# inv_schem.net
KiCad netlist of a schematic drawn in Altium Designer
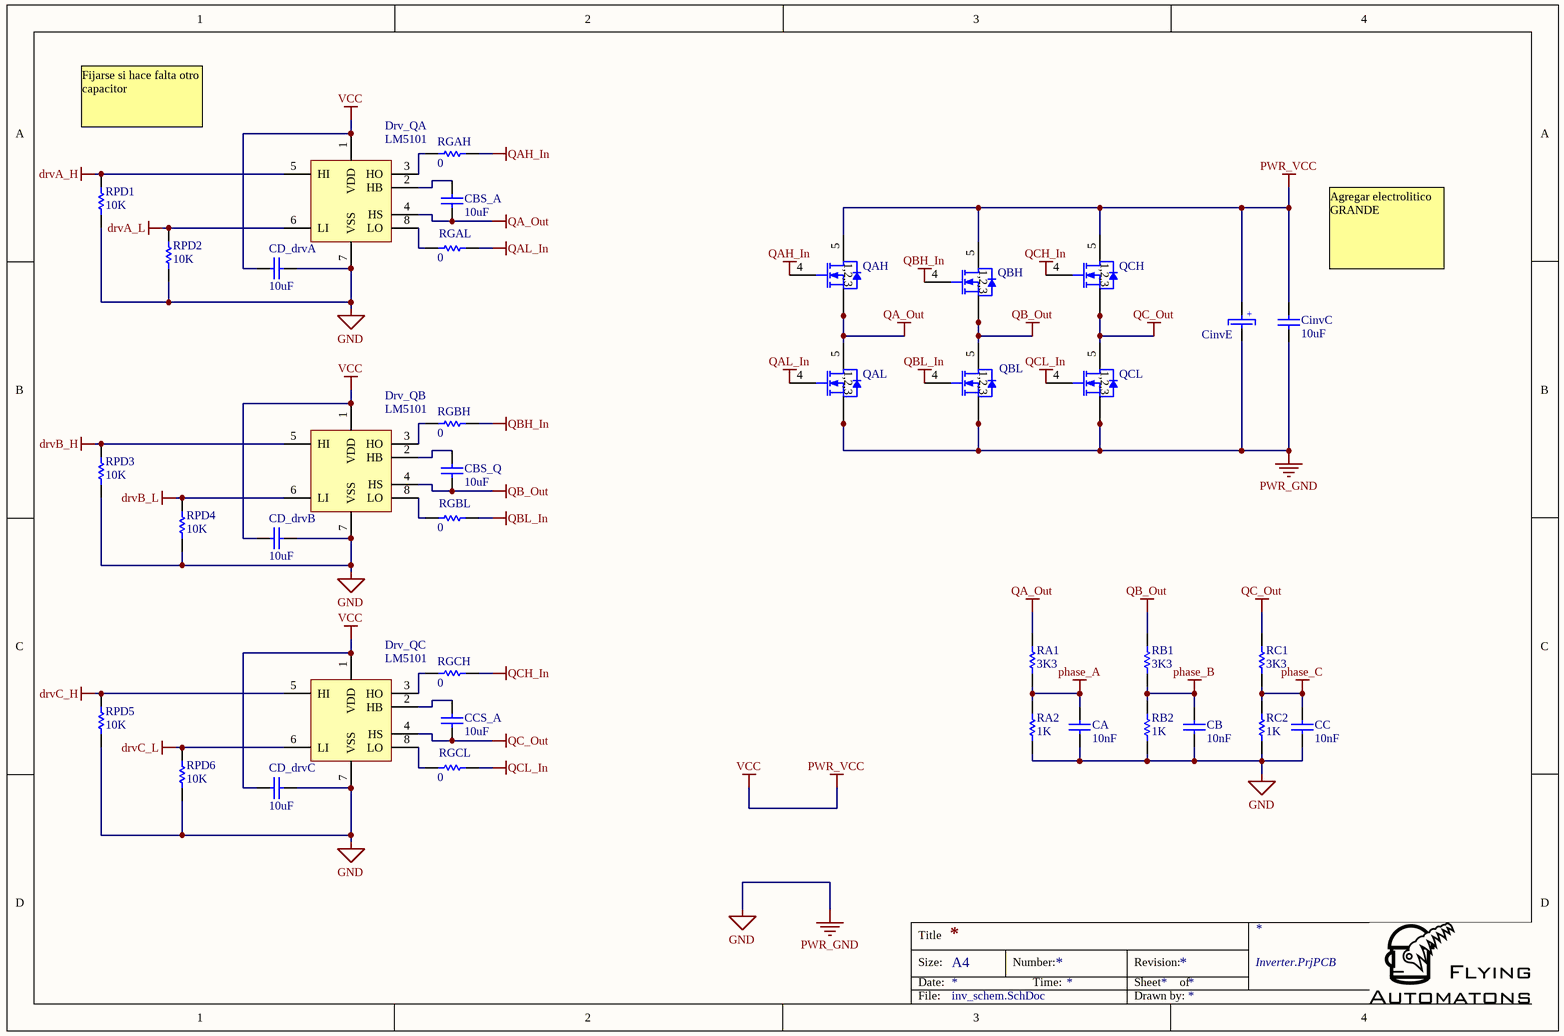
[diagram p0: inv_schem.SchDoc]

(export (version "E")
  (design (tool "Eeschema 10.0.6"))
  (components
    (comp (ref "CA")
      (value "10nF")
      (footprint "CAPC1608L")
      (description "CAP CER 0.1UF 50V Y5V 0603")
      (fields (field (name "MANUFACTURER PART NUMBER") "CC0603ZRY5V9BB104"))
      (libsource (lib "Passive#csv") (part "CAP_100n_0603_50V_Y5V"))
    )
    (comp (ref "CB")
      (value "10nF")
      (footprint "CAPC1608L")
      (description "CAP CER 0.1UF 50V Y5V 0603")
      (fields (field (name "MANUFACTURER PART NUMBER") "CC0603ZRY5V9BB104"))
      (libsource (lib "Passive#csv") (part "CAP_100n_0603_50V_Y5V"))
    )
    (comp (ref "CBS_A")
      (value "10uF")
      (footprint "CAPC3216L")
      (description "CAP CER 10UF 25V Y5V 1206")
      (fields (field (name "MANUFACTURER PART NUMBER") "TMK316F106ZL-T"))
      (libsource (lib "Passive#csv") (part "CAP_10u_1206_25V_Y5V"))
    )
    (comp (ref "CBS_Q")
      (value "10uF")
      (footprint "CAPC3216L")
      (description "CAP CER 10UF 25V Y5V 1206")
      (fields (field (name "MANUFACTURER PART NUMBER") "TMK316F106ZL-T"))
      (libsource (lib "Passive#csv") (part "CAP_10u_1206_25V_Y5V"))
    )
    (comp (ref "CC")
      (value "10nF")
      (footprint "CAPC1608L")
      (description "CAP CER 0.1UF 50V Y5V 0603")
      (fields (field (name "MANUFACTURER PART NUMBER") "CC0603ZRY5V9BB104"))
      (libsource (lib "Passive#csv") (part "CAP_100n_0603_50V_Y5V"))
    )
    (comp (ref "CCS_A")
      (value "10uF")
      (footprint "CAPC3216L")
      (description "CAP CER 10UF 25V Y5V 1206")
      (fields (field (name "MANUFACTURER PART NUMBER") "TMK316F106ZL-T"))
      (libsource (lib "Passive#csv") (part "CAP_10u_1206_25V_Y5V"))
    )
    (comp (ref "CD_drvA")
      (value "10uF")
      (footprint "CAPC3216L")
      (description "CAP CER 10UF 25V Y5V 1206")
      (fields (field (name "MANUFACTURER PART NUMBER") "TMK316F106ZL-T"))
      (libsource (lib "Passive#csv") (part "CAP_10u_1206_25V_Y5V"))
    )
    (comp (ref "CD_drvB")
      (value "10uF")
      (footprint "CAPC3216L")
      (description "CAP CER 10UF 25V Y5V 1206")
      (fields (field (name "MANUFACTURER PART NUMBER") "TMK316F106ZL-T"))
      (libsource (lib "Passive#csv") (part "CAP_10u_1206_25V_Y5V"))
    )
    (comp (ref "CD_drvC")
      (value "10uF")
      (footprint "CAPC3216L")
      (description "CAP CER 10UF 25V Y5V 1206")
      (fields (field (name "MANUFACTURER PART NUMBER") "TMK316F106ZL-T"))
      (libsource (lib "Passive#csv") (part "CAP_10u_1206_25V_Y5V"))
    )
    (comp (ref "CinvC")
      (value "10uF")
      (footprint "CAPC3216L")
      (description "CAP CER 10UF 25V Y5V 1206")
      (fields (field (name "MANUFACTURER PART NUMBER") "TMK316F106ZL-T"))
      (libsource (lib "Passive#csv") (part "CAP_10u_1206_25V_Y5V"))
    )
    (comp (ref "CinvE")
      (value "SMD_ECap")
      (footprint "SMD ECap")
      (description "100uF")
      (libsource (lib "smd") (part "SMD_ECap"))
    )
    (comp (ref "Drv_QA")
      (value "LM5101")
      (footprint "JEDEC_MS-012AA")
      (description "100V 2A N-Channel MOSFET Gate Driver")
      (fields
        (field (name "MANUFACTURER PART NUMBER") "LM5101BMA-NOPB")
        (field (name "MANUFACTURER") "Texas Instruments")
      )
      (libsource (lib "Power_IC#csv") (part "LM5101"))
    )
    (comp (ref "Drv_QB")
      (value "LM5101")
      (footprint "JEDEC_MS-012AA")
      (description "100V 2A N-Channel MOSFET Gate Driver")
      (fields
        (field (name "MANUFACTURER PART NUMBER") "LM5101BMA-NOPB")
        (field (name "MANUFACTURER") "Texas Instruments")
      )
      (libsource (lib "Power_IC#csv") (part "LM5101"))
    )
    (comp (ref "Drv_QC")
      (value "LM5101")
      (footprint "JEDEC_MS-012AA")
      (description "100V 2A N-Channel MOSFET Gate Driver")
      (fields
        (field (name "MANUFACTURER PART NUMBER") "LM5101BMA-NOPB")
        (field (name "MANUFACTURER") "Texas Instruments")
      )
      (libsource (lib "Power_IC#csv") (part "LM5101"))
    )
    (comp (ref "QAH")
      (value "~")
      (footprint "x-NXP_LFPAK33")
      (description "TRANSISTOR MOSFET N-CHANN 25V 8.6MOHM")
      (fields
        (field (name "MANUFACTURER") "NXP Semiconductors")
        (field (name "MANUFACTURER PART NUMBER") "PSMN9R0-25MLC,115")
      )
      (libsource (lib "Discrete#csv") (part "PSMN9R0-25MLC"))
    )
    (comp (ref "QAL")
      (value "~")
      (footprint "x-NXP_LFPAK33")
      (description "TRANSISTOR MOSFET N-CHANN 25V 8.6MOHM")
      (fields
        (field (name "MANUFACTURER") "NXP Semiconductors")
        (field (name "MANUFACTURER PART NUMBER") "PSMN9R0-25MLC,115")
      )
      (libsource (lib "Discrete#csv") (part "PSMN9R0-25MLC"))
    )
    (comp (ref "QBH")
      (value "~")
      (footprint "x-NXP_LFPAK33")
      (description "TRANSISTOR MOSFET N-CHANN 25V 8.6MOHM")
      (fields
        (field (name "MANUFACTURER") "NXP Semiconductors")
        (field (name "MANUFACTURER PART NUMBER") "PSMN9R0-25MLC,115")
      )
      (libsource (lib "Discrete#csv") (part "PSMN9R0-25MLC"))
    )
    (comp (ref "QBL")
      (value "~")
      (footprint "x-NXP_LFPAK33")
      (description "TRANSISTOR MOSFET N-CHANN 25V 8.6MOHM")
      (fields
        (field (name "MANUFACTURER") "NXP Semiconductors")
        (field (name "MANUFACTURER PART NUMBER") "PSMN9R0-25MLC,115")
      )
      (libsource (lib "Discrete#csv") (part "PSMN9R0-25MLC"))
    )
    (comp (ref "QCH")
      (value "~")
      (footprint "x-NXP_LFPAK33")
      (description "TRANSISTOR MOSFET N-CHANN 25V 8.6MOHM")
      (fields
        (field (name "MANUFACTURER") "NXP Semiconductors")
        (field (name "MANUFACTURER PART NUMBER") "PSMN9R0-25MLC,115")
      )
      (libsource (lib "Discrete#csv") (part "PSMN9R0-25MLC"))
    )
    (comp (ref "QCL")
      (value "~")
      (footprint "x-NXP_LFPAK33")
      (description "TRANSISTOR MOSFET N-CHANN 25V 8.6MOHM")
      (fields
        (field (name "MANUFACTURER") "NXP Semiconductors")
        (field (name "MANUFACTURER PART NUMBER") "PSMN9R0-25MLC,115")
      )
      (libsource (lib "Discrete#csv") (part "PSMN9R0-25MLC"))
    )
    (comp (ref "RA1")
      (value "3K3")
      (footprint "RESC1608L")
      (description "RES 1K OHM 1/10W 5% 0603")
      (fields (field (name "MANUFACTURER PART NUMBER") "RMCF0603JT1K00"))
      (libsource (lib "Passive#csv") (part "RES_1K_0603_0W1_1%"))
    )
    (comp (ref "RA2")
      (value "1K")
      (footprint "RESC1608L")
      (description "RES 1K OHM 1/10W 5% 0603")
      (fields (field (name "MANUFACTURER PART NUMBER") "RMCF0603JT1K00"))
      (libsource (lib "Passive#csv") (part "RES_1K_0603_0W1_1%"))
    )
    (comp (ref "RB1")
      (value "3K3")
      (footprint "RESC1608L")
      (description "RES 1K OHM 1/10W 5% 0603")
      (fields (field (name "MANUFACTURER PART NUMBER") "RMCF0603JT1K00"))
      (libsource (lib "Passive#csv") (part "RES_1K_0603_0W1_1%"))
    )
    (comp (ref "RB2")
      (value "1K")
      (footprint "RESC1608L")
      (description "RES 1K OHM 1/10W 5% 0603")
      (fields (field (name "MANUFACTURER PART NUMBER") "RMCF0603JT1K00"))
      (libsource (lib "Passive#csv") (part "RES_1K_0603_0W1_1%"))
    )
    (comp (ref "RC1")
      (value "3K3")
      (footprint "RESC1608L")
      (description "RES 1K OHM 1/10W 5% 0603")
      (fields (field (name "MANUFACTURER PART NUMBER") "RMCF0603JT1K00"))
      (libsource (lib "Passive#csv") (part "RES_1K_0603_0W1_1%"))
    )
    (comp (ref "RC2")
      (value "1K")
      (footprint "RESC1608L")
      (description "RES 1K OHM 1/10W 5% 0603")
      (fields (field (name "MANUFACTURER PART NUMBER") "RMCF0603JT1K00"))
      (libsource (lib "Passive#csv") (part "RES_1K_0603_0W1_1%"))
    )
    (comp (ref "RGAH")
      (value "0")
      (footprint "RESC1608L")
      (description "RES 0.0 OHM 1/10W JUMP 0603")
      (fields (field (name "MANUFACTURER PART NUMBER") "RC1608J000CS"))
      (libsource (lib "Passive#csv") (part "RES_0_0603_0W1_1%"))
    )
    (comp (ref "RGAL")
      (value "0")
      (footprint "RESC1608L")
      (description "RES 0.0 OHM 1/10W JUMP 0603")
      (fields (field (name "MANUFACTURER PART NUMBER") "RC1608J000CS"))
      (libsource (lib "Passive#csv") (part "RES_0_0603_0W1_1%"))
    )
    (comp (ref "RGBH")
      (value "0")
      (footprint "RESC1608L")
      (description "RES 0.0 OHM 1/10W JUMP 0603")
      (fields (field (name "MANUFACTURER PART NUMBER") "RC1608J000CS"))
      (libsource (lib "Passive#csv") (part "RES_0_0603_0W1_1%"))
    )
    (comp (ref "RGBL")
      (value "0")
      (footprint "RESC1608L")
      (description "RES 0.0 OHM 1/10W JUMP 0603")
      (fields (field (name "MANUFACTURER PART NUMBER") "RC1608J000CS"))
      (libsource (lib "Passive#csv") (part "RES_0_0603_0W1_1%"))
    )
    (comp (ref "RGCH")
      (value "0")
      (footprint "RESC1608L")
      (description "RES 0.0 OHM 1/10W JUMP 0603")
      (fields (field (name "MANUFACTURER PART NUMBER") "RC1608J000CS"))
      (libsource (lib "Passive#csv") (part "RES_0_0603_0W1_1%"))
    )
    (comp (ref "RGCL")
      (value "0")
      (footprint "RESC1608L")
      (description "RES 0.0 OHM 1/10W JUMP 0603")
      (fields (field (name "MANUFACTURER PART NUMBER") "RC1608J000CS"))
      (libsource (lib "Passive#csv") (part "RES_0_0603_0W1_1%"))
    )
    (comp (ref "RPD1")
      (value "10K")
      (footprint "RESC1608L")
      (description "RES 10K OHM 1/10W 5% 0603")
      (fields (field (name "MANUFACTURER PART NUMBER") "RC1608J103CS"))
      (libsource (lib "Passive#csv") (part "RES_10K_0603_0W1_1%"))
    )
    (comp (ref "RPD2")
      (value "10K")
      (footprint "RESC1608L")
      (description "RES 10K OHM 1/10W 5% 0603")
      (fields (field (name "MANUFACTURER PART NUMBER") "RC1608J103CS"))
      (libsource (lib "Passive#csv") (part "RES_10K_0603_0W1_1%"))
    )
    (comp (ref "RPD3")
      (value "10K")
      (footprint "RESC1608L")
      (description "RES 10K OHM 1/10W 5% 0603")
      (fields (field (name "MANUFACTURER PART NUMBER") "RC1608J103CS"))
      (libsource (lib "Passive#csv") (part "RES_10K_0603_0W1_1%"))
    )
    (comp (ref "RPD4")
      (value "10K")
      (footprint "RESC1608L")
      (description "RES 10K OHM 1/10W 5% 0603")
      (fields (field (name "MANUFACTURER PART NUMBER") "RC1608J103CS"))
      (libsource (lib "Passive#csv") (part "RES_10K_0603_0W1_1%"))
    )
    (comp (ref "RPD5")
      (value "10K")
      (footprint "RESC1608L")
      (description "RES 10K OHM 1/10W 5% 0603")
      (fields (field (name "MANUFACTURER PART NUMBER") "RC1608J103CS"))
      (libsource (lib "Passive#csv") (part "RES_10K_0603_0W1_1%"))
    )
    (comp (ref "RPD6")
      (value "10K")
      (footprint "RESC1608L")
      (description "RES 10K OHM 1/10W 5% 0603")
      (fields (field (name "MANUFACTURER PART NUMBER") "RC1608J103CS"))
      (libsource (lib "Passive#csv") (part "RES_10K_0603_0W1_1%"))
    )
  )
  (nets
    (net (code "1") (name "GND") (class "Default")
      (node (ref "CA") (pin "2") (pinfunction "2_2") (pintype "passive"))
      (node (ref "CB") (pin "2") (pinfunction "2_2") (pintype "passive"))
      (node (ref "CC") (pin "2") (pinfunction "2_2") (pintype "passive"))
      (node (ref "CD_drvA") (pin "2") (pinfunction "2_2") (pintype "passive"))
      (node (ref "CD_drvB") (pin "2") (pinfunction "2_2") (pintype "passive"))
      (node (ref "CD_drvC") (pin "2") (pinfunction "2_2") (pintype "passive"))
      (node (ref "CinvC") (pin "2") (pinfunction "2_2") (pintype "passive"))
      (node (ref "CinvE") (pin "2") (pinfunction "2_2") (pintype "passive"))
      (node (ref "Drv_QA") (pin "7") (pinfunction "VSS_7") (pintype "passive"))
      (node (ref "Drv_QB") (pin "7") (pinfunction "VSS_7") (pintype "passive"))
      (node (ref "Drv_QC") (pin "7") (pinfunction "VSS_7") (pintype "passive"))
      (node (ref "QAL") (pin "1") (pinfunction "S_1") (pintype "passive"))
      (node (ref "QAL") (pin "2") (pinfunction "S_2") (pintype "passive"))
      (node (ref "QAL") (pin "3") (pinfunction "S_3") (pintype "passive"))
      (node (ref "QBL") (pin "1") (pinfunction "S_1") (pintype "passive"))
      (node (ref "QBL") (pin "2") (pinfunction "S_2") (pintype "passive"))
      (node (ref "QBL") (pin "3") (pinfunction "S_3") (pintype "passive"))
      (node (ref "QCL") (pin "1") (pinfunction "S_1") (pintype "passive"))
      (node (ref "QCL") (pin "2") (pinfunction "S_2") (pintype "passive"))
      (node (ref "QCL") (pin "3") (pinfunction "S_3") (pintype "passive"))
      (node (ref "RA2") (pin "2") (pinfunction "2_2") (pintype "passive"))
      (node (ref "RB2") (pin "2") (pinfunction "2_2") (pintype "passive"))
      (node (ref "RC2") (pin "2") (pinfunction "2_2") (pintype "passive"))
      (node (ref "RPD1") (pin "2") (pinfunction "2_2") (pintype "passive"))
      (node (ref "RPD2") (pin "2") (pinfunction "2_2") (pintype "passive"))
      (node (ref "RPD3") (pin "2") (pinfunction "2_2") (pintype "passive"))
      (node (ref "RPD4") (pin "2") (pinfunction "2_2") (pintype "passive"))
      (node (ref "RPD5") (pin "2") (pinfunction "2_2") (pintype "passive"))
      (node (ref "RPD6") (pin "2") (pinfunction "2_2") (pintype "passive"))
    )
    (net (code "2") (name "Net-(Drv_QA-HB)") (class "Default")
      (node (ref "CBS_A") (pin "1") (pinfunction "1_1") (pintype "passive"))
      (node (ref "Drv_QA") (pin "2") (pinfunction "HB_2") (pintype "passive"))
    )
    (net (code "3") (name "Net-(Drv_QA-HO)") (class "Default")
      (node (ref "Drv_QA") (pin "3") (pinfunction "HO_3") (pintype "passive"))
      (node (ref "RGAH") (pin "2") (pinfunction "2_2") (pintype "passive"))
    )
    (net (code "4") (name "Net-(Drv_QA-LO)") (class "Default")
      (node (ref "Drv_QA") (pin "8") (pinfunction "LO_8") (pintype "passive"))
      (node (ref "RGAL") (pin "2") (pinfunction "2_2") (pintype "passive"))
    )
    (net (code "5") (name "Net-(Drv_QB-HB)") (class "Default")
      (node (ref "CBS_Q") (pin "1") (pinfunction "1_1") (pintype "passive"))
      (node (ref "Drv_QB") (pin "2") (pinfunction "HB_2") (pintype "passive"))
    )
    (net (code "6") (name "Net-(Drv_QB-HO)") (class "Default")
      (node (ref "Drv_QB") (pin "3") (pinfunction "HO_3") (pintype "passive"))
      (node (ref "RGBH") (pin "2") (pinfunction "2_2") (pintype "passive"))
    )
    (net (code "7") (name "Net-(Drv_QB-LO)") (class "Default")
      (node (ref "Drv_QB") (pin "8") (pinfunction "LO_8") (pintype "passive"))
      (node (ref "RGBL") (pin "2") (pinfunction "2_2") (pintype "passive"))
    )
    (net (code "8") (name "Net-(Drv_QC-HB)") (class "Default")
      (node (ref "CCS_A") (pin "1") (pinfunction "1_1") (pintype "passive"))
      (node (ref "Drv_QC") (pin "2") (pinfunction "HB_2") (pintype "passive"))
    )
    (net (code "9") (name "Net-(Drv_QC-HO)") (class "Default")
      (node (ref "Drv_QC") (pin "3") (pinfunction "HO_3") (pintype "passive"))
      (node (ref "RGCH") (pin "2") (pinfunction "2_2") (pintype "passive"))
    )
    (net (code "10") (name "Net-(Drv_QC-LO)") (class "Default")
      (node (ref "Drv_QC") (pin "8") (pinfunction "LO_8") (pintype "passive"))
      (node (ref "RGCL") (pin "2") (pinfunction "2_2") (pintype "passive"))
    )
    (net (code "11") (name "PWR_VCC") (class "Default")
      (node (ref "CD_drvA") (pin "1") (pinfunction "1_1") (pintype "passive"))
      (node (ref "CD_drvB") (pin "1") (pinfunction "1_1") (pintype "passive"))
      (node (ref "CD_drvC") (pin "1") (pinfunction "1_1") (pintype "passive"))
      (node (ref "CinvC") (pin "1") (pinfunction "1_1") (pintype "passive"))
      (node (ref "CinvE") (pin "1") (pinfunction "1_1") (pintype "passive"))
      (node (ref "Drv_QA") (pin "1") (pinfunction "VDD_1") (pintype "passive"))
      (node (ref "Drv_QB") (pin "1") (pinfunction "VDD_1") (pintype "passive"))
      (node (ref "Drv_QC") (pin "1") (pinfunction "VDD_1") (pintype "passive"))
      (node (ref "QAH") (pin "5") (pinfunction "D_5") (pintype "passive"))
      (node (ref "QBH") (pin "5") (pinfunction "D_5") (pintype "passive"))
      (node (ref "QCH") (pin "5") (pinfunction "D_5") (pintype "passive"))
    )
    (net (code "12") (name "QAH_In") (class "Default")
      (node (ref "QAH") (pin "4") (pinfunction "G_4") (pintype "passive"))
      (node (ref "RGAH") (pin "1") (pinfunction "1_1") (pintype "passive"))
    )
    (net (code "13") (name "QAL_In") (class "Default")
      (node (ref "QAL") (pin "4") (pinfunction "G_4") (pintype "passive"))
      (node (ref "RGAL") (pin "1") (pinfunction "1_1") (pintype "passive"))
    )
    (net (code "14") (name "QA_Out") (class "Default")
      (node (ref "CBS_A") (pin "2") (pinfunction "2_2") (pintype "passive"))
      (node (ref "Drv_QA") (pin "4") (pinfunction "HS_4") (pintype "passive"))
      (node (ref "QAH") (pin "1") (pinfunction "S_1") (pintype "passive"))
      (node (ref "QAH") (pin "2") (pinfunction "S_2") (pintype "passive"))
      (node (ref "QAH") (pin "3") (pinfunction "S_3") (pintype "passive"))
      (node (ref "QAL") (pin "5") (pinfunction "D_5") (pintype "passive"))
      (node (ref "RA1") (pin "1") (pinfunction "1_1") (pintype "passive"))
    )
    (net (code "15") (name "QBH_In") (class "Default")
      (node (ref "QBH") (pin "4") (pinfunction "G_4") (pintype "passive"))
      (node (ref "RGBH") (pin "1") (pinfunction "1_1") (pintype "passive"))
    )
    (net (code "16") (name "QBL_In") (class "Default")
      (node (ref "QBL") (pin "4") (pinfunction "G_4") (pintype "passive"))
      (node (ref "RGBL") (pin "1") (pinfunction "1_1") (pintype "passive"))
    )
    (net (code "17") (name "QB_Out") (class "Default")
      (node (ref "CBS_Q") (pin "2") (pinfunction "2_2") (pintype "passive"))
      (node (ref "Drv_QB") (pin "4") (pinfunction "HS_4") (pintype "passive"))
      (node (ref "QBH") (pin "1") (pinfunction "S_1") (pintype "passive"))
      (node (ref "QBH") (pin "2") (pinfunction "S_2") (pintype "passive"))
      (node (ref "QBH") (pin "3") (pinfunction "S_3") (pintype "passive"))
      (node (ref "QBL") (pin "5") (pinfunction "D_5") (pintype "passive"))
      (node (ref "RB1") (pin "1") (pinfunction "1_1") (pintype "passive"))
    )
    (net (code "18") (name "QCH_In") (class "Default")
      (node (ref "QCH") (pin "4") (pinfunction "G_4") (pintype "passive"))
      (node (ref "RGCH") (pin "1") (pinfunction "1_1") (pintype "passive"))
    )
    (net (code "19") (name "QCL_In") (class "Default")
      (node (ref "QCL") (pin "4") (pinfunction "G_4") (pintype "passive"))
      (node (ref "RGCL") (pin "1") (pinfunction "1_1") (pintype "passive"))
    )
    (net (code "20") (name "QC_Out") (class "Default")
      (node (ref "CCS_A") (pin "2") (pinfunction "2_2") (pintype "passive"))
      (node (ref "Drv_QC") (pin "4") (pinfunction "HS_4") (pintype "passive"))
      (node (ref "QCH") (pin "1") (pinfunction "S_1") (pintype "passive"))
      (node (ref "QCH") (pin "2") (pinfunction "S_2") (pintype "passive"))
      (node (ref "QCH") (pin "3") (pinfunction "S_3") (pintype "passive"))
      (node (ref "QCL") (pin "5") (pinfunction "D_5") (pintype "passive"))
      (node (ref "RC1") (pin "1") (pinfunction "1_1") (pintype "passive"))
    )
    (net (code "21") (name "drvA_H") (class "Default")
      (node (ref "Drv_QA") (pin "5") (pinfunction "HI_5") (pintype "passive"))
      (node (ref "RPD1") (pin "1") (pinfunction "1_1") (pintype "passive"))
    )
    (net (code "22") (name "drvA_L") (class "Default")
      (node (ref "Drv_QA") (pin "6") (pinfunction "LI_6") (pintype "passive"))
      (node (ref "RPD2") (pin "1") (pinfunction "1_1") (pintype "passive"))
    )
    (net (code "23") (name "drvB_H") (class "Default")
      (node (ref "Drv_QB") (pin "5") (pinfunction "HI_5") (pintype "passive"))
      (node (ref "RPD3") (pin "1") (pinfunction "1_1") (pintype "passive"))
    )
    (net (code "24") (name "drvB_L") (class "Default")
      (node (ref "Drv_QB") (pin "6") (pinfunction "LI_6") (pintype "passive"))
      (node (ref "RPD4") (pin "1") (pinfunction "1_1") (pintype "passive"))
    )
    (net (code "25") (name "drvC_H") (class "Default")
      (node (ref "Drv_QC") (pin "5") (pinfunction "HI_5") (pintype "passive"))
      (node (ref "RPD5") (pin "1") (pinfunction "1_1") (pintype "passive"))
    )
    (net (code "26") (name "drvC_L") (class "Default")
      (node (ref "Drv_QC") (pin "6") (pinfunction "LI_6") (pintype "passive"))
      (node (ref "RPD6") (pin "1") (pinfunction "1_1") (pintype "passive"))
    )
    (net (code "27") (name "phase_A") (class "Default")
      (node (ref "CA") (pin "1") (pinfunction "1_1") (pintype "passive"))
      (node (ref "RA1") (pin "2") (pinfunction "2_2") (pintype "passive"))
      (node (ref "RA2") (pin "1") (pinfunction "1_1") (pintype "passive"))
    )
    (net (code "28") (name "phase_B") (class "Default")
      (node (ref "CB") (pin "1") (pinfunction "1_1") (pintype "passive"))
      (node (ref "RB1") (pin "2") (pinfunction "2_2") (pintype "passive"))
      (node (ref "RB2") (pin "1") (pinfunction "1_1") (pintype "passive"))
    )
    (net (code "29") (name "phase_C") (class "Default")
      (node (ref "CC") (pin "1") (pinfunction "1_1") (pintype "passive"))
      (node (ref "RC1") (pin "2") (pinfunction "2_2") (pintype "passive"))
      (node (ref "RC2") (pin "1") (pinfunction "1_1") (pintype "passive"))
    )
  )
)
